# ApoBoard_2017_V10.net
KiCad netlist of a schematic drawn in EAGLE
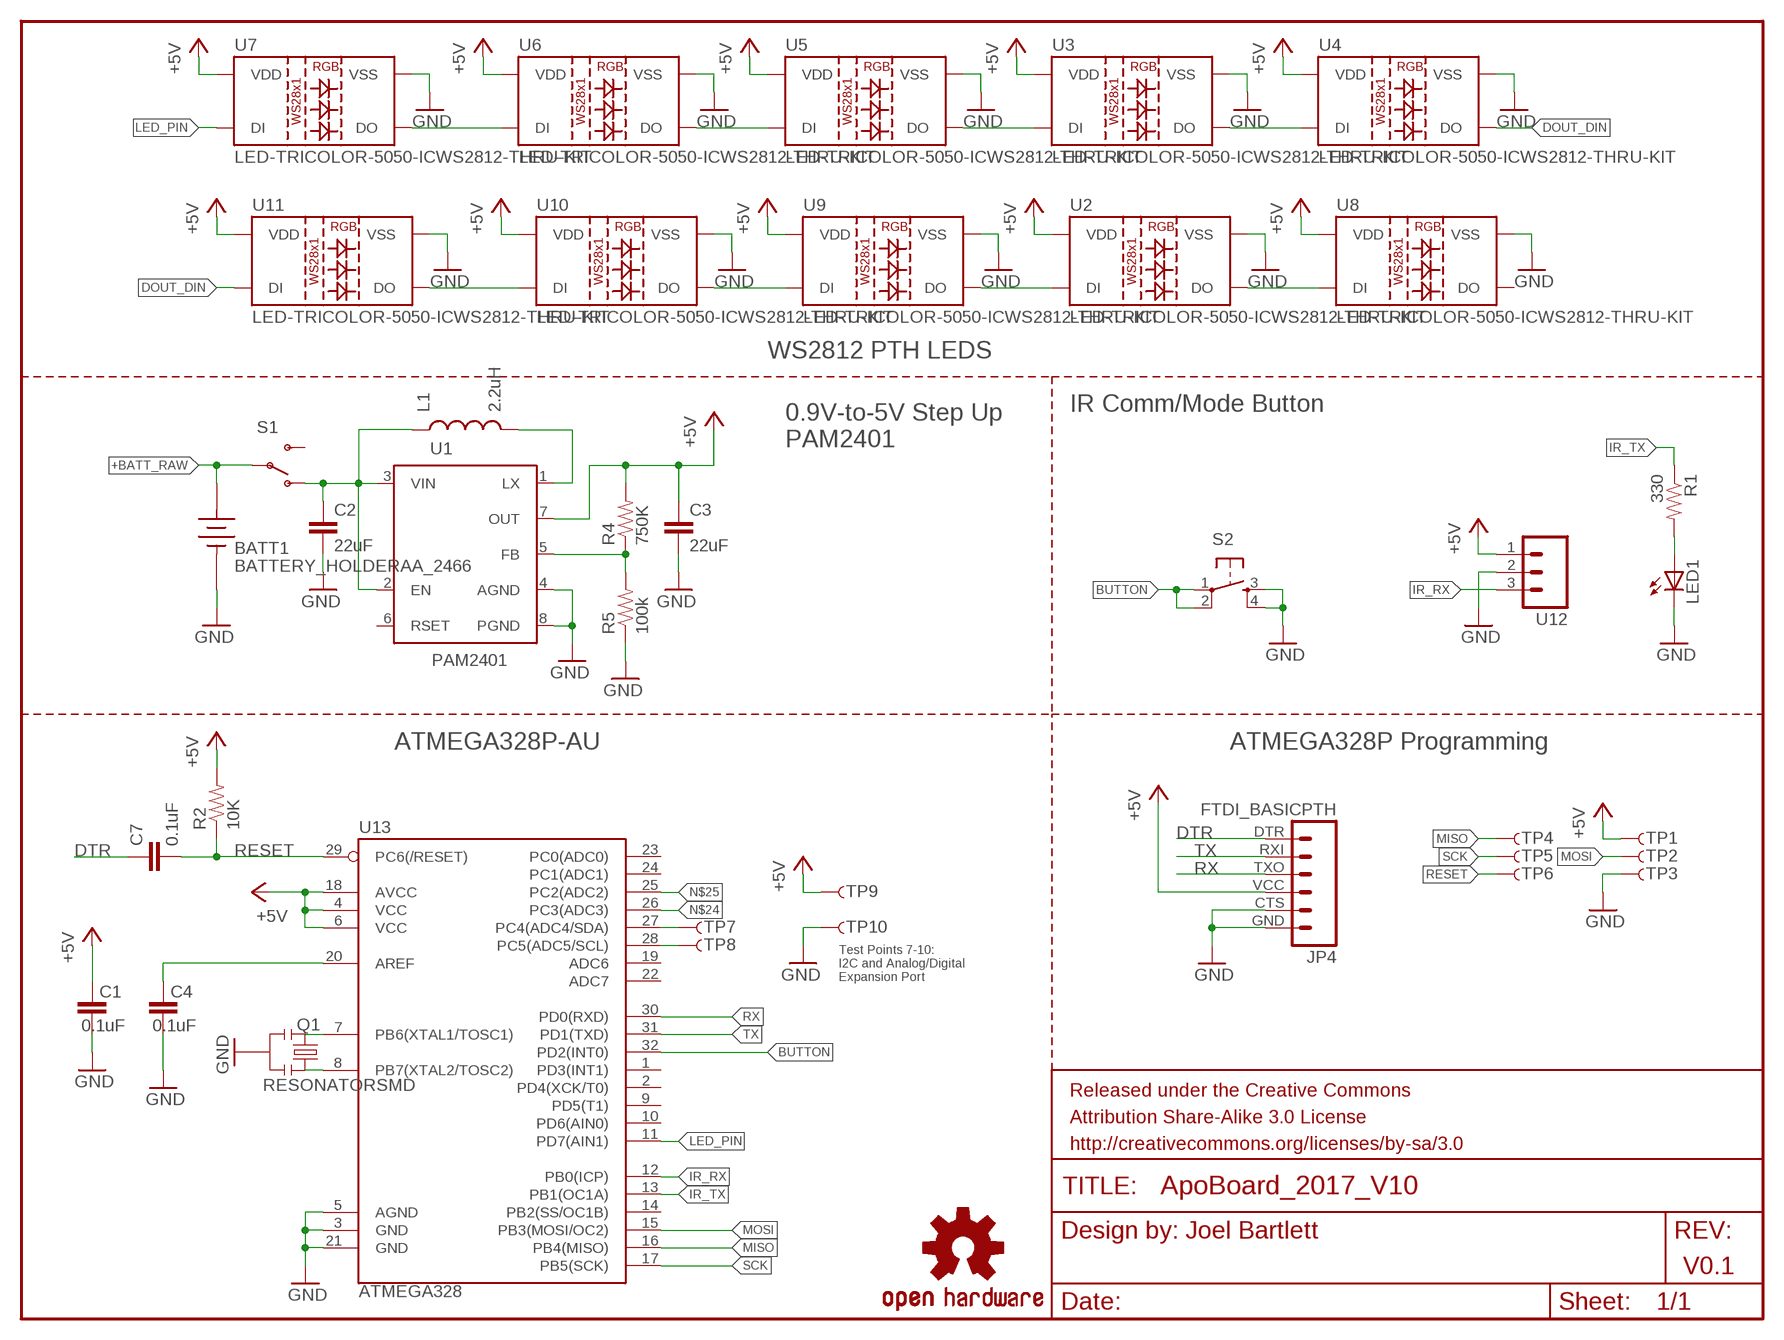
[diagram p0: schematic, sheet 1]

(export (version "E")
  (design (tool "Eeschema 10.0.6"))
  (components
    (comp (ref "BATT1")
      (value "BATTERY_HOLDERAA_2466")
      (footprint "eagle-import:BATT_HOLDER_AA_2466")
      (libsource (lib "eagle-import") (part "BATTERY_HOLDERAA_2466"))
    )
    (comp (ref "C1")
      (value "0.1uF")
      (footprint "eagle-import:0402-CAP")
      (libsource (lib "eagle-import") (part "CAP0402-CAP"))
    )
    (comp (ref "C2")
      (value "22uF")
      (footprint "eagle-import:0805")
      (libsource (lib "eagle-import") (part "22UF-6.3V-20%(0805)"))
    )
    (comp (ref "C3")
      (value "22uF")
      (footprint "eagle-import:0805")
      (libsource (lib "eagle-import") (part "22UF-6.3V-20%(0805)"))
    )
    (comp (ref "C4")
      (value "0.1uF")
      (footprint "eagle-import:0402-CAP")
      (libsource (lib "eagle-import") (part "CAP0402-CAP"))
    )
    (comp (ref "C7")
      (value "0.1uF")
      (footprint "eagle-import:0402-CAP")
      (libsource (lib "eagle-import") (part "CAP0402-CAP"))
    )
    (comp (ref "FRAME1")
      (value "FRAME-LETTER")
      (footprint "eagle-import:CREATIVE_COMMONS")
      (libsource (lib "eagle-import") (part "FRAME-LETTER"))
    )
    (comp (ref "JP4")
      (value "FTDI_BASICPTH")
      (footprint "eagle-import:FTDI_BASIC")
      (libsource (lib "eagle-import") (part "FTDI_BASICPTH"))
    )
    (comp (ref "L1")
      (value "2.2uH")
      (footprint "eagle-import:CDRH2D09")
      (libsource (lib "eagle-import") (part "INDUCTOR."))
    )
    (comp (ref "LED1")
      (value "LED5MM-KIT")
      (footprint "eagle-import:LED5MM-KIT")
      (libsource (lib "eagle-import") (part "LED5MM-KIT"))
    )
    (comp (ref "LOGO1")
      (value "OSHW-LOGOS")
      (footprint "eagle-import:OSHW-LOGO-S")
      (libsource (lib "eagle-import") (part "OSHW-LOGOS"))
    )
    (comp (ref "Q1")
      (value "RESONATORSMD")
      (footprint "eagle-import:RESONATOR-SMD")
      (libsource (lib "eagle-import") (part "RESONATORSMD"))
    )
    (comp (ref "R1")
      (value "330")
      (footprint "eagle-import:AXIAL-0.3-KIT")
      (libsource (lib "eagle-import") (part "SparkFun-Resistors_RESISTORKIT"))
    )
    (comp (ref "R2")
      (value "10K")
      (footprint "eagle-import:0402-RES")
      (libsource (lib "eagle-import") (part "RESISTOR0402-RES"))
    )
    (comp (ref "R4")
      (value "750K")
      (footprint "eagle-import:0603-RES")
      (libsource (lib "eagle-import") (part "10K-1%RES-00824"))
    )
    (comp (ref "R5")
      (value "100k")
      (footprint "eagle-import:0603-RES")
      (libsource (lib "eagle-import") (part "10K-1%RES-00824"))
    )
    (comp (ref "S1")
      (value "SWITCH-SPSTKIT")
      (footprint "eagle-import:SWITCH-SPDT_KIT")
      (libsource (lib "eagle-import") (part "SWITCH-SPSTKIT"))
    )
    (comp (ref "S2")
      (value "TAC_SWITCHPTH")
      (footprint "eagle-import:TACTILE-PTH")
      (libsource (lib "eagle-import") (part "TAC_SWITCHPTH"))
    )
    (comp (ref "TP1")
      (value "TP-3x5")
      (footprint "eagle-import:PAD.03X.05")
      (libsource (lib "eagle-import") (part "TEST-POINT3X5"))
    )
    (comp (ref "TP2")
      (value "TP-3x5")
      (footprint "eagle-import:PAD.03X.05")
      (libsource (lib "eagle-import") (part "TEST-POINT3X5"))
    )
    (comp (ref "TP3")
      (value "TP-3x5")
      (footprint "eagle-import:PAD.03X.05")
      (libsource (lib "eagle-import") (part "TEST-POINT3X5"))
    )
    (comp (ref "TP4")
      (value "TP-3x5")
      (footprint "eagle-import:PAD.03X.05")
      (libsource (lib "eagle-import") (part "TEST-POINT3X5"))
    )
    (comp (ref "TP5")
      (value "TP-3x5")
      (footprint "eagle-import:PAD.03X.05")
      (libsource (lib "eagle-import") (part "TEST-POINT3X5"))
    )
    (comp (ref "TP6")
      (value "TP-3x5")
      (footprint "eagle-import:PAD.03X.05")
      (libsource (lib "eagle-import") (part "TEST-POINT3X5"))
    )
    (comp (ref "TP7")
      (value "TP-3x5")
      (footprint "eagle-import:PAD.03X.05")
      (libsource (lib "eagle-import") (part "TEST-POINT3X5"))
    )
    (comp (ref "TP8")
      (value "TP-3x5")
      (footprint "eagle-import:PAD.03X.05")
      (libsource (lib "eagle-import") (part "TEST-POINT3X5"))
    )
    (comp (ref "TP9")
      (value "TP-3x5")
      (footprint "eagle-import:PAD.03X.05")
      (libsource (lib "eagle-import") (part "TEST-POINT3X5"))
    )
    (comp (ref "TP10")
      (value "TP-3x5")
      (footprint "eagle-import:PAD.03X.05")
      (libsource (lib "eagle-import") (part "TEST-POINT3X5"))
    )
    (comp (ref "U1")
      (value "PAM2401")
      (footprint "eagle-import:MSOP8")
      (libsource (lib "eagle-import") (part "PAM2401"))
    )
    (comp (ref "U2")
      (value "LED-TRICOLOR-5050-ICWS2812-THRU-KIT")
      (footprint "eagle-import:LED-RGB-THRU-KIT")
      (libsource (lib "eagle-import") (part "LED-TRICOLOR-5050-ICWS2812-THRU-KIT"))
    )
    (comp (ref "U3")
      (value "LED-TRICOLOR-5050-ICWS2812-THRU-KIT")
      (footprint "eagle-import:LED-RGB-THRU-KIT")
      (libsource (lib "eagle-import") (part "LED-TRICOLOR-5050-ICWS2812-THRU-KIT"))
    )
    (comp (ref "U4")
      (value "LED-TRICOLOR-5050-ICWS2812-THRU-KIT")
      (footprint "eagle-import:LED-RGB-THRU-KIT")
      (libsource (lib "eagle-import") (part "LED-TRICOLOR-5050-ICWS2812-THRU-KIT"))
    )
    (comp (ref "U5")
      (value "LED-TRICOLOR-5050-ICWS2812-THRU-KIT")
      (footprint "eagle-import:LED-RGB-THRU-KIT")
      (libsource (lib "eagle-import") (part "LED-TRICOLOR-5050-ICWS2812-THRU-KIT"))
    )
    (comp (ref "U6")
      (value "LED-TRICOLOR-5050-ICWS2812-THRU-KIT")
      (footprint "eagle-import:LED-RGB-THRU-KIT")
      (libsource (lib "eagle-import") (part "LED-TRICOLOR-5050-ICWS2812-THRU-KIT"))
    )
    (comp (ref "U7")
      (value "LED-TRICOLOR-5050-ICWS2812-THRU-KIT")
      (footprint "eagle-import:LED-RGB-THRU-KIT")
      (libsource (lib "eagle-import") (part "LED-TRICOLOR-5050-ICWS2812-THRU-KIT"))
    )
    (comp (ref "U8")
      (value "LED-TRICOLOR-5050-ICWS2812-THRU-KIT")
      (footprint "eagle-import:LED-RGB-THRU-KIT")
      (libsource (lib "eagle-import") (part "LED-TRICOLOR-5050-ICWS2812-THRU-KIT"))
    )
    (comp (ref "U9")
      (value "LED-TRICOLOR-5050-ICWS2812-THRU-KIT")
      (footprint "eagle-import:LED-RGB-THRU-KIT")
      (libsource (lib "eagle-import") (part "LED-TRICOLOR-5050-ICWS2812-THRU-KIT"))
    )
    (comp (ref "U10")
      (value "LED-TRICOLOR-5050-ICWS2812-THRU-KIT")
      (footprint "eagle-import:LED-RGB-THRU-KIT")
      (libsource (lib "eagle-import") (part "LED-TRICOLOR-5050-ICWS2812-THRU-KIT"))
    )
    (comp (ref "U11")
      (value "LED-TRICOLOR-5050-ICWS2812-THRU-KIT")
      (footprint "eagle-import:LED-RGB-THRU-KIT")
      (libsource (lib "eagle-import") (part "LED-TRICOLOR-5050-ICWS2812-THRU-KIT"))
    )
    (comp (ref "U12")
      (value "M03IR_RECEIVER")
      (footprint "eagle-import:1X03_IR_RECEIVER")
      (libsource (lib "eagle-import") (part "M03IR_RECEIVER"))
    )
    (comp (ref "U13")
      (value "ATMEGA328")
      (footprint "eagle-import:TQFP32-08")
      (libsource (lib "eagle-import") (part "ATMEGA168"))
    )
  )
  (nets
    (net (code "1") (name "+5V") (class "Default")
      (node (ref "C1") (pin "2") (pinfunction "2_2") (pintype "passive"))
      (node (ref "C3") (pin "1") (pinfunction "1_1") (pintype "passive"))
      (node (ref "JP4") (pin "VCC") (pinfunction "4_VCC") (pintype "passive"))
      (node (ref "R2") (pin "2") (pinfunction "2_2") (pintype "passive"))
      (node (ref "R4") (pin "2") (pinfunction "2_2") (pintype "passive"))
      (node (ref "TP1") (pin "P$1") (pinfunction "1_P$1") (pintype "bidirectional"))
      (node (ref "TP9") (pin "P$1") (pinfunction "1_P$1") (pintype "bidirectional"))
      (node (ref "U1") (pin "7") (pinfunction "OUT_7") (pintype "bidirectional"))
      (node (ref "U10") (pin "2") (pinfunction "VDD_2") (pintype "bidirectional"))
      (node (ref "U11") (pin "2") (pinfunction "VDD_2") (pintype "bidirectional"))
      (node (ref "U12") (pin "1") (pinfunction "1_1") (pintype "passive"))
      (node (ref "U13") (pin "18") (pinfunction "AVCC_18") (pintype "bidirectional"))
      (node (ref "U13") (pin "4") (pinfunction "VCC_4") (pintype "bidirectional"))
      (node (ref "U13") (pin "6") (pinfunction "VCC_6") (pintype "bidirectional"))
      (node (ref "U2") (pin "2") (pinfunction "VDD_2") (pintype "bidirectional"))
      (node (ref "U3") (pin "2") (pinfunction "VDD_2") (pintype "bidirectional"))
      (node (ref "U4") (pin "2") (pinfunction "VDD_2") (pintype "bidirectional"))
      (node (ref "U5") (pin "2") (pinfunction "VDD_2") (pintype "bidirectional"))
      (node (ref "U6") (pin "2") (pinfunction "VDD_2") (pintype "bidirectional"))
      (node (ref "U7") (pin "2") (pinfunction "VDD_2") (pintype "bidirectional"))
      (node (ref "U8") (pin "2") (pinfunction "VDD_2") (pintype "bidirectional"))
      (node (ref "U9") (pin "2") (pinfunction "VDD_2") (pintype "bidirectional"))
    )
    (net (code "2") (name "+BATT_RAW") (class "Default")
      (node (ref "BATT1") (pin "P") (pinfunction "P_P") (pintype "bidirectional"))
      (node (ref "S1") (pin "2") (pinfunction "P_2") (pintype "passive"))
    )
    (net (code "3") (name "/DTR") (class "Default")
      (node (ref "C7") (pin "1") (pinfunction "1_1") (pintype "passive"))
      (node (ref "JP4") (pin "DTR") (pinfunction "1_DTR") (pintype "passive"))
    )
    (net (code "4") (name "BUTTON") (class "Default")
      (node (ref "S2") (pin "1") (pinfunction "1_1") (pintype "passive"))
      (node (ref "S2") (pin "2") (pinfunction "2_2") (pintype "passive"))
      (node (ref "U13") (pin "32") (pinfunction "PD2(INT0)_32") (pintype "bidirectional"))
    )
    (net (code "5") (name "DOUT_DIN") (class "Default")
      (node (ref "U11") (pin "1") (pinfunction "DI_1") (pintype "bidirectional"))
      (node (ref "U4") (pin "4") (pinfunction "DO_4") (pintype "bidirectional"))
    )
    (net (code "6") (name "GND") (class "Default")
      (node (ref "BATT1") (pin "N") (pinfunction "N_N") (pintype "bidirectional"))
      (node (ref "C1") (pin "1") (pinfunction "1_1") (pintype "passive"))
      (node (ref "C2") (pin "2") (pinfunction "2_2") (pintype "passive"))
      (node (ref "C3") (pin "2") (pinfunction "2_2") (pintype "passive"))
      (node (ref "C4") (pin "1") (pinfunction "1_1") (pintype "passive"))
      (node (ref "JP4") (pin "CTS") (pinfunction "5_CTS") (pintype "passive"))
      (node (ref "JP4") (pin "GND") (pinfunction "6_GND") (pintype "passive"))
      (node (ref "LED1") (pin "K") (pinfunction "C_K") (pintype "passive"))
      (node (ref "Q1") (pin "2") (pinfunction "2_2") (pintype "passive"))
      (node (ref "R5") (pin "1") (pinfunction "1_1") (pintype "passive"))
      (node (ref "S2") (pin "3") (pinfunction "3_3") (pintype "passive"))
      (node (ref "S2") (pin "4") (pinfunction "4_4") (pintype "passive"))
      (node (ref "TP10") (pin "P$1") (pinfunction "1_P$1") (pintype "bidirectional"))
      (node (ref "TP3") (pin "P$1") (pinfunction "1_P$1") (pintype "bidirectional"))
      (node (ref "U1") (pin "4") (pinfunction "AGND_4") (pintype "bidirectional"))
      (node (ref "U1") (pin "8") (pinfunction "PGND_8") (pintype "bidirectional"))
      (node (ref "U10") (pin "3") (pinfunction "VSS_3") (pintype "bidirectional"))
      (node (ref "U11") (pin "3") (pinfunction "VSS_3") (pintype "bidirectional"))
      (node (ref "U12") (pin "2") (pinfunction "2_2") (pintype "passive"))
      (node (ref "U13") (pin "21") (pinfunction "GND_21") (pintype "bidirectional"))
      (node (ref "U13") (pin "3") (pinfunction "GND_3") (pintype "bidirectional"))
      (node (ref "U13") (pin "5") (pinfunction "AGND_5") (pintype "bidirectional"))
      (node (ref "U2") (pin "3") (pinfunction "VSS_3") (pintype "bidirectional"))
      (node (ref "U3") (pin "3") (pinfunction "VSS_3") (pintype "bidirectional"))
      (node (ref "U4") (pin "3") (pinfunction "VSS_3") (pintype "bidirectional"))
      (node (ref "U5") (pin "3") (pinfunction "VSS_3") (pintype "bidirectional"))
      (node (ref "U6") (pin "3") (pinfunction "VSS_3") (pintype "bidirectional"))
      (node (ref "U7") (pin "3") (pinfunction "VSS_3") (pintype "bidirectional"))
      (node (ref "U8") (pin "3") (pinfunction "VSS_3") (pintype "bidirectional"))
      (node (ref "U9") (pin "3") (pinfunction "VSS_3") (pintype "bidirectional"))
    )
    (net (code "7") (name "IR_RX") (class "Default")
      (node (ref "U12") (pin "3") (pinfunction "3_3") (pintype "passive"))
      (node (ref "U13") (pin "12") (pinfunction "PB0(ICP)_12") (pintype "bidirectional"))
    )
    (net (code "8") (name "IR_TX") (class "Default")
      (node (ref "R1") (pin "P$1") (pinfunction "1_P$1") (pintype "passive"))
      (node (ref "U13") (pin "13") (pinfunction "PB1(OC1A)_13") (pintype "bidirectional"))
    )
    (net (code "9") (name "LED_PIN") (class "Default")
      (node (ref "U13") (pin "11") (pinfunction "PD7(AIN1)_11") (pintype "bidirectional"))
      (node (ref "U7") (pin "1") (pinfunction "DI_1") (pintype "bidirectional"))
    )
    (net (code "10") (name "MISO") (class "Default")
      (node (ref "TP4") (pin "P$1") (pinfunction "1_P$1") (pintype "bidirectional"))
      (node (ref "U13") (pin "16") (pinfunction "PB4(MISO)_16") (pintype "bidirectional"))
    )
    (net (code "11") (name "MOSI") (class "Default")
      (node (ref "TP2") (pin "P$1") (pinfunction "1_P$1") (pintype "bidirectional"))
      (node (ref "U13") (pin "15") (pinfunction "PB3(MOSI/OC2)_15") (pintype "bidirectional"))
    )
    (net (code "12") (name "N$24") (class "Default")
      (node (ref "U13") (pin "26") (pinfunction "PC3(ADC3)_26") (pintype "bidirectional"))
    )
    (net (code "13") (name "N$25") (class "Default")
      (node (ref "U13") (pin "25") (pinfunction "PC2(ADC2)_25") (pintype "bidirectional"))
    )
    (net (code "14") (name "Net-(L1-1)") (class "Default")
      (node (ref "C2") (pin "1") (pinfunction "1_1") (pintype "passive"))
      (node (ref "L1") (pin "P$1") (pinfunction "1_P$1") (pintype "passive"))
      (node (ref "S1") (pin "1") (pinfunction "O_1") (pintype "passive"))
      (node (ref "U1") (pin "2") (pinfunction "EN_2") (pintype "bidirectional"))
      (node (ref "U1") (pin "3") (pinfunction "VIN_3") (pintype "bidirectional"))
    )
    (net (code "15") (name "Net-(L1-2)") (class "Default")
      (node (ref "L1") (pin "P$2") (pinfunction "2_P$2") (pintype "passive"))
      (node (ref "U1") (pin "1") (pinfunction "LX_1") (pintype "bidirectional"))
    )
    (net (code "16") (name "Net-(R1-2)") (class "Default")
      (node (ref "LED1") (pin "A") (pinfunction "A_A") (pintype "passive"))
      (node (ref "R1") (pin "P$2") (pinfunction "2_P$2") (pintype "passive"))
    )
    (net (code "17") (name "Net-(TP7-1)") (class "Default")
      (node (ref "TP7") (pin "P$1") (pinfunction "1_P$1") (pintype "bidirectional"))
      (node (ref "U13") (pin "27") (pinfunction "PC4(ADC4/SDA)_27") (pintype "bidirectional"))
    )
    (net (code "18") (name "Net-(TP8-1)") (class "Default")
      (node (ref "TP8") (pin "P$1") (pinfunction "1_P$1") (pintype "bidirectional"))
      (node (ref "U13") (pin "28") (pinfunction "PC5(ADC5/SCL)_28") (pintype "bidirectional"))
    )
    (net (code "19") (name "Net-(U1-FB)") (class "Default")
      (node (ref "R4") (pin "1") (pinfunction "1_1") (pintype "passive"))
      (node (ref "R5") (pin "2") (pinfunction "2_2") (pintype "passive"))
      (node (ref "U1") (pin "5") (pinfunction "FB_5") (pintype "bidirectional"))
    )
    (net (code "20") (name "Net-(U2-DI)") (class "Default")
      (node (ref "U2") (pin "1") (pinfunction "DI_1") (pintype "bidirectional"))
      (node (ref "U9") (pin "4") (pinfunction "DO_4") (pintype "bidirectional"))
    )
    (net (code "21") (name "Net-(U2-DO)") (class "Default")
      (node (ref "U2") (pin "4") (pinfunction "DO_4") (pintype "bidirectional"))
      (node (ref "U8") (pin "1") (pinfunction "DI_1") (pintype "bidirectional"))
    )
    (net (code "22") (name "Net-(U3-DI)") (class "Default")
      (node (ref "U3") (pin "1") (pinfunction "DI_1") (pintype "bidirectional"))
      (node (ref "U5") (pin "4") (pinfunction "DO_4") (pintype "bidirectional"))
    )
    (net (code "23") (name "Net-(U3-DO)") (class "Default")
      (node (ref "U3") (pin "4") (pinfunction "DO_4") (pintype "bidirectional"))
      (node (ref "U4") (pin "1") (pinfunction "DI_1") (pintype "bidirectional"))
    )
    (net (code "24") (name "Net-(U5-DI)") (class "Default")
      (node (ref "U5") (pin "1") (pinfunction "DI_1") (pintype "bidirectional"))
      (node (ref "U6") (pin "4") (pinfunction "DO_4") (pintype "bidirectional"))
    )
    (net (code "25") (name "Net-(U6-DI)") (class "Default")
      (node (ref "U6") (pin "1") (pinfunction "DI_1") (pintype "bidirectional"))
      (node (ref "U7") (pin "4") (pinfunction "DO_4") (pintype "bidirectional"))
    )
    (net (code "26") (name "Net-(U10-DI)") (class "Default")
      (node (ref "U10") (pin "1") (pinfunction "DI_1") (pintype "bidirectional"))
      (node (ref "U11") (pin "4") (pinfunction "DO_4") (pintype "bidirectional"))
    )
    (net (code "27") (name "Net-(U10-DO)") (class "Default")
      (node (ref "U10") (pin "4") (pinfunction "DO_4") (pintype "bidirectional"))
      (node (ref "U9") (pin "1") (pinfunction "DI_1") (pintype "bidirectional"))
    )
    (net (code "28") (name "Net-(U13-AREF)") (class "Default")
      (node (ref "C4") (pin "2") (pinfunction "2_2") (pintype "passive"))
      (node (ref "U13") (pin "20") (pinfunction "AREF_20") (pintype "bidirectional"))
    )
    (net (code "29") (name "Net-(U13-PB6(XTAL1{slash}TOSC1))") (class "Default")
      (node (ref "Q1") (pin "3") (pinfunction "3_3") (pintype "passive"))
      (node (ref "U13") (pin "7") (pinfunction "PB6(XTAL1/TOSC1)_7") (pintype "bidirectional"))
    )
    (net (code "30") (name "Net-(U13-PB7(XTAL2{slash}TOSC2))") (class "Default")
      (node (ref "Q1") (pin "1") (pinfunction "1_1") (pintype "passive"))
      (node (ref "U13") (pin "8") (pinfunction "PB7(XTAL2/TOSC2)_8") (pintype "bidirectional"))
    )
    (net (code "31") (name "RESET") (class "Default")
      (node (ref "C7") (pin "2") (pinfunction "2_2") (pintype "passive"))
      (node (ref "R2") (pin "1") (pinfunction "1_1") (pintype "passive"))
      (node (ref "TP6") (pin "P$1") (pinfunction "1_P$1") (pintype "bidirectional"))
      (node (ref "U13") (pin "29") (pinfunction "PC6(/RESET)_29") (pintype "bidirectional"))
    )
    (net (code "32") (name "RX") (class "Default")
      (node (ref "JP4") (pin "TXO") (pinfunction "3_TXO") (pintype "passive"))
      (node (ref "U13") (pin "30") (pinfunction "PD0(RXD)_30") (pintype "bidirectional"))
    )
    (net (code "33") (name "SCK") (class "Default")
      (node (ref "TP5") (pin "P$1") (pinfunction "1_P$1") (pintype "bidirectional"))
      (node (ref "U13") (pin "17") (pinfunction "PB5(SCK)_17") (pintype "bidirectional"))
    )
    (net (code "34") (name "TX") (class "Default")
      (node (ref "JP4") (pin "RXI") (pinfunction "2_RXI") (pintype "passive"))
      (node (ref "U13") (pin "31") (pinfunction "PD1(TXD)_31") (pintype "bidirectional"))
    )
    (net (code "35") (name "unconnected-(S1-S-Pad3)") (class "Default")
      (node (ref "S1") (pin "3") (pinfunction "S_3") (pintype "passive"))
    )
    (net (code "36") (name "unconnected-(U1-RSET-Pad6)") (class "Default")
      (node (ref "U1") (pin "6") (pinfunction "RSET_6") (pintype "bidirectional"))
    )
    (net (code "37") (name "unconnected-(U8-DO-Pad4)") (class "Default")
      (node (ref "U8") (pin "4") (pinfunction "DO_4") (pintype "bidirectional"))
    )
    (net (code "38") (name "unconnected-(U13-ADC6-Pad19)") (class "Default")
      (node (ref "U13") (pin "19") (pinfunction "ADC6_19") (pintype "bidirectional"))
    )
    (net (code "39") (name "unconnected-(U13-ADC7-Pad22)") (class "Default")
      (node (ref "U13") (pin "22") (pinfunction "ADC7_22") (pintype "bidirectional"))
    )
    (net (code "40") (name "unconnected-(U13-PB2(SS{slash}OC1B)-Pad14)") (class "Default")
      (node (ref "U13") (pin "14") (pinfunction "PB2(SS/OC1B)_14") (pintype "bidirectional"))
    )
    (net (code "41") (name "unconnected-(U13-PC0(ADC0)-Pad23)") (class "Default")
      (node (ref "U13") (pin "23") (pinfunction "PC0(ADC0)_23") (pintype "bidirectional"))
    )
    (net (code "42") (name "unconnected-(U13-PC1(ADC1)-Pad24)") (class "Default")
      (node (ref "U13") (pin "24") (pinfunction "PC1(ADC1)_24") (pintype "bidirectional"))
    )
    (net (code "43") (name "unconnected-(U13-PD3(INT1)-Pad1)") (class "Default")
      (node (ref "U13") (pin "1") (pinfunction "PD3(INT1)_1") (pintype "bidirectional"))
    )
    (net (code "44") (name "unconnected-(U13-PD4(XCK{slash}T0)-Pad2)") (class "Default")
      (node (ref "U13") (pin "2") (pinfunction "PD4(XCK/T0)_2") (pintype "bidirectional"))
    )
    (net (code "45") (name "unconnected-(U13-PD5(T1)-Pad9)") (class "Default")
      (node (ref "U13") (pin "9") (pinfunction "PD5(T1)_9") (pintype "bidirectional"))
    )
    (net (code "46") (name "unconnected-(U13-PD6(AIN0)-Pad10)") (class "Default")
      (node (ref "U13") (pin "10") (pinfunction "PD6(AIN0)_10") (pintype "bidirectional"))
    )
  )
)
